# Arduino_R3_Half_Template.net
KiCad netlist of a schematic drawn in EAGLE
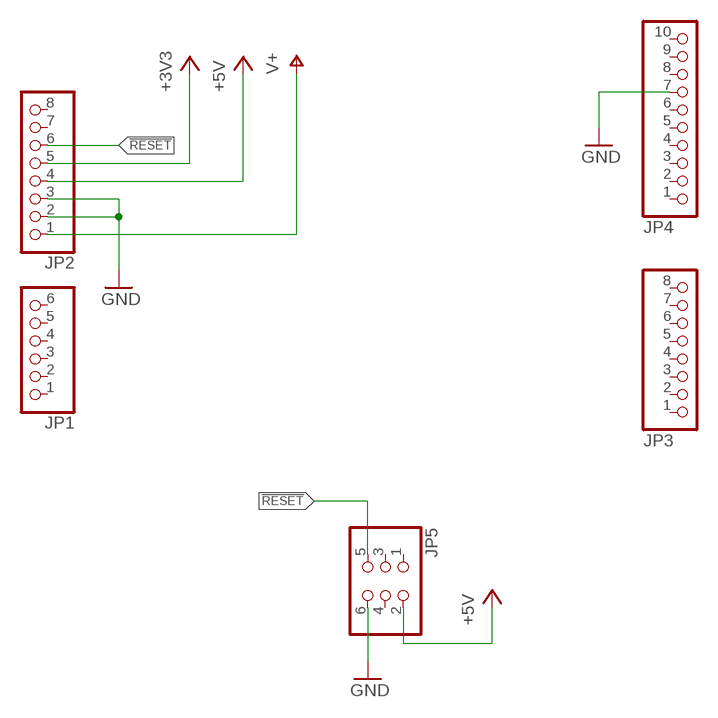
[diagram p0: schematic, sheet 1]

(export (version "E")
  (design (tool "Eeschema 10.0.6"))
  (components
    (comp (ref "JP1")
      (value "PINHD-1X6")
      (footprint "eagle-import:1X06")
      (libsource (lib "eagle-import") (part "PINHD-1X6"))
    )
    (comp (ref "JP2")
      (value "PINHD-1X8")
      (footprint "eagle-import:1X08")
      (libsource (lib "eagle-import") (part "PINHD-1X8"))
    )
    (comp (ref "JP3")
      (value "PINHD-1X8")
      (footprint "eagle-import:1X08")
      (libsource (lib "eagle-import") (part "PINHD-1X8"))
    )
    (comp (ref "JP4")
      (value "PINHD-1X10")
      (footprint "eagle-import:1X10")
      (libsource (lib "eagle-import") (part "PINHD-1X10"))
    )
    (comp (ref "JP5")
      (value "PINHD-2X3")
      (footprint "eagle-import:2X03")
      (libsource (lib "eagle-import") (part "PINHD-2X3"))
    )
  )
  (nets
    (net (code "1") (name "+3V3") (class "Default")
      (node (ref "JP2") (pin "5") (pinfunction "5_5") (pintype "passive"))
    )
    (net (code "2") (name "+5V") (class "Default")
      (node (ref "JP2") (pin "4") (pinfunction "4_4") (pintype "passive"))
      (node (ref "JP5") (pin "2") (pinfunction "2_2") (pintype "passive"))
    )
    (net (code "3") (name "/~{RESET}") (class "Default")
      (node (ref "JP2") (pin "6") (pinfunction "6_6") (pintype "passive"))
      (node (ref "JP5") (pin "5") (pinfunction "5_5") (pintype "passive"))
    )
    (net (code "4") (name "GND") (class "Default")
      (node (ref "JP2") (pin "2") (pinfunction "2_2") (pintype "passive"))
      (node (ref "JP2") (pin "3") (pinfunction "3_3") (pintype "passive"))
      (node (ref "JP4") (pin "7") (pinfunction "7_7") (pintype "passive"))
      (node (ref "JP5") (pin "6") (pinfunction "6_6") (pintype "passive"))
    )
    (net (code "5") (name "V+") (class "Default")
      (node (ref "JP2") (pin "1") (pinfunction "1_1") (pintype "passive"))
    )
    (net (code "6") (name "unconnected-(JP1-Pad1)") (class "Default")
      (node (ref "JP1") (pin "1") (pinfunction "1_1") (pintype "passive"))
    )
    (net (code "7") (name "unconnected-(JP1-Pad2)") (class "Default")
      (node (ref "JP1") (pin "2") (pinfunction "2_2") (pintype "passive"))
    )
    (net (code "8") (name "unconnected-(JP1-Pad3)") (class "Default")
      (node (ref "JP1") (pin "3") (pinfunction "3_3") (pintype "passive"))
    )
    (net (code "9") (name "unconnected-(JP1-Pad4)") (class "Default")
      (node (ref "JP1") (pin "4") (pinfunction "4_4") (pintype "passive"))
    )
    (net (code "10") (name "unconnected-(JP1-Pad5)") (class "Default")
      (node (ref "JP1") (pin "5") (pinfunction "5_5") (pintype "passive"))
    )
    (net (code "11") (name "unconnected-(JP1-Pad6)") (class "Default")
      (node (ref "JP1") (pin "6") (pinfunction "6_6") (pintype "passive"))
    )
    (net (code "12") (name "unconnected-(JP2-Pad7)") (class "Default")
      (node (ref "JP2") (pin "7") (pinfunction "7_7") (pintype "passive"))
    )
    (net (code "13") (name "unconnected-(JP2-Pad8)") (class "Default")
      (node (ref "JP2") (pin "8") (pinfunction "8_8") (pintype "passive"))
    )
    (net (code "14") (name "unconnected-(JP3-Pad1)") (class "Default")
      (node (ref "JP3") (pin "1") (pinfunction "1_1") (pintype "passive"))
    )
    (net (code "15") (name "unconnected-(JP3-Pad2)") (class "Default")
      (node (ref "JP3") (pin "2") (pinfunction "2_2") (pintype "passive"))
    )
    (net (code "16") (name "unconnected-(JP3-Pad3)") (class "Default")
      (node (ref "JP3") (pin "3") (pinfunction "3_3") (pintype "passive"))
    )
    (net (code "17") (name "unconnected-(JP3-Pad4)") (class "Default")
      (node (ref "JP3") (pin "4") (pinfunction "4_4") (pintype "passive"))
    )
    (net (code "18") (name "unconnected-(JP3-Pad5)") (class "Default")
      (node (ref "JP3") (pin "5") (pinfunction "5_5") (pintype "passive"))
    )
    (net (code "19") (name "unconnected-(JP3-Pad6)") (class "Default")
      (node (ref "JP3") (pin "6") (pinfunction "6_6") (pintype "passive"))
    )
    (net (code "20") (name "unconnected-(JP3-Pad7)") (class "Default")
      (node (ref "JP3") (pin "7") (pinfunction "7_7") (pintype "passive"))
    )
    (net (code "21") (name "unconnected-(JP3-Pad8)") (class "Default")
      (node (ref "JP3") (pin "8") (pinfunction "8_8") (pintype "passive"))
    )
    (net (code "22") (name "unconnected-(JP4-Pad1)") (class "Default")
      (node (ref "JP4") (pin "1") (pinfunction "1_1") (pintype "passive"))
    )
    (net (code "23") (name "unconnected-(JP4-Pad2)") (class "Default")
      (node (ref "JP4") (pin "2") (pinfunction "2_2") (pintype "passive"))
    )
    (net (code "24") (name "unconnected-(JP4-Pad3)") (class "Default")
      (node (ref "JP4") (pin "3") (pinfunction "3_3") (pintype "passive"))
    )
    (net (code "25") (name "unconnected-(JP4-Pad4)") (class "Default")
      (node (ref "JP4") (pin "4") (pinfunction "4_4") (pintype "passive"))
    )
    (net (code "26") (name "unconnected-(JP4-Pad5)") (class "Default")
      (node (ref "JP4") (pin "5") (pinfunction "5_5") (pintype "passive"))
    )
    (net (code "27") (name "unconnected-(JP4-Pad6)") (class "Default")
      (node (ref "JP4") (pin "6") (pinfunction "6_6") (pintype "passive"))
    )
    (net (code "28") (name "unconnected-(JP4-Pad8)") (class "Default")
      (node (ref "JP4") (pin "8") (pinfunction "8_8") (pintype "passive"))
    )
    (net (code "29") (name "unconnected-(JP4-Pad9)") (class "Default")
      (node (ref "JP4") (pin "9") (pinfunction "9_9") (pintype "passive"))
    )
    (net (code "30") (name "unconnected-(JP4-Pad10)") (class "Default")
      (node (ref "JP4") (pin "10") (pinfunction "10_10") (pintype "passive"))
    )
    (net (code "31") (name "unconnected-(JP5-Pad1)") (class "Default")
      (node (ref "JP5") (pin "1") (pinfunction "1_1") (pintype "passive"))
    )
    (net (code "32") (name "unconnected-(JP5-Pad3)") (class "Default")
      (node (ref "JP5") (pin "3") (pinfunction "3_3") (pintype "passive"))
    )
    (net (code "33") (name "unconnected-(JP5-Pad4)") (class "Default")
      (node (ref "JP5") (pin "4") (pinfunction "4_4") (pintype "passive"))
    )
  )
)
